# Collection.net
KiCad netlist of a schematic drawn in Altium Designer
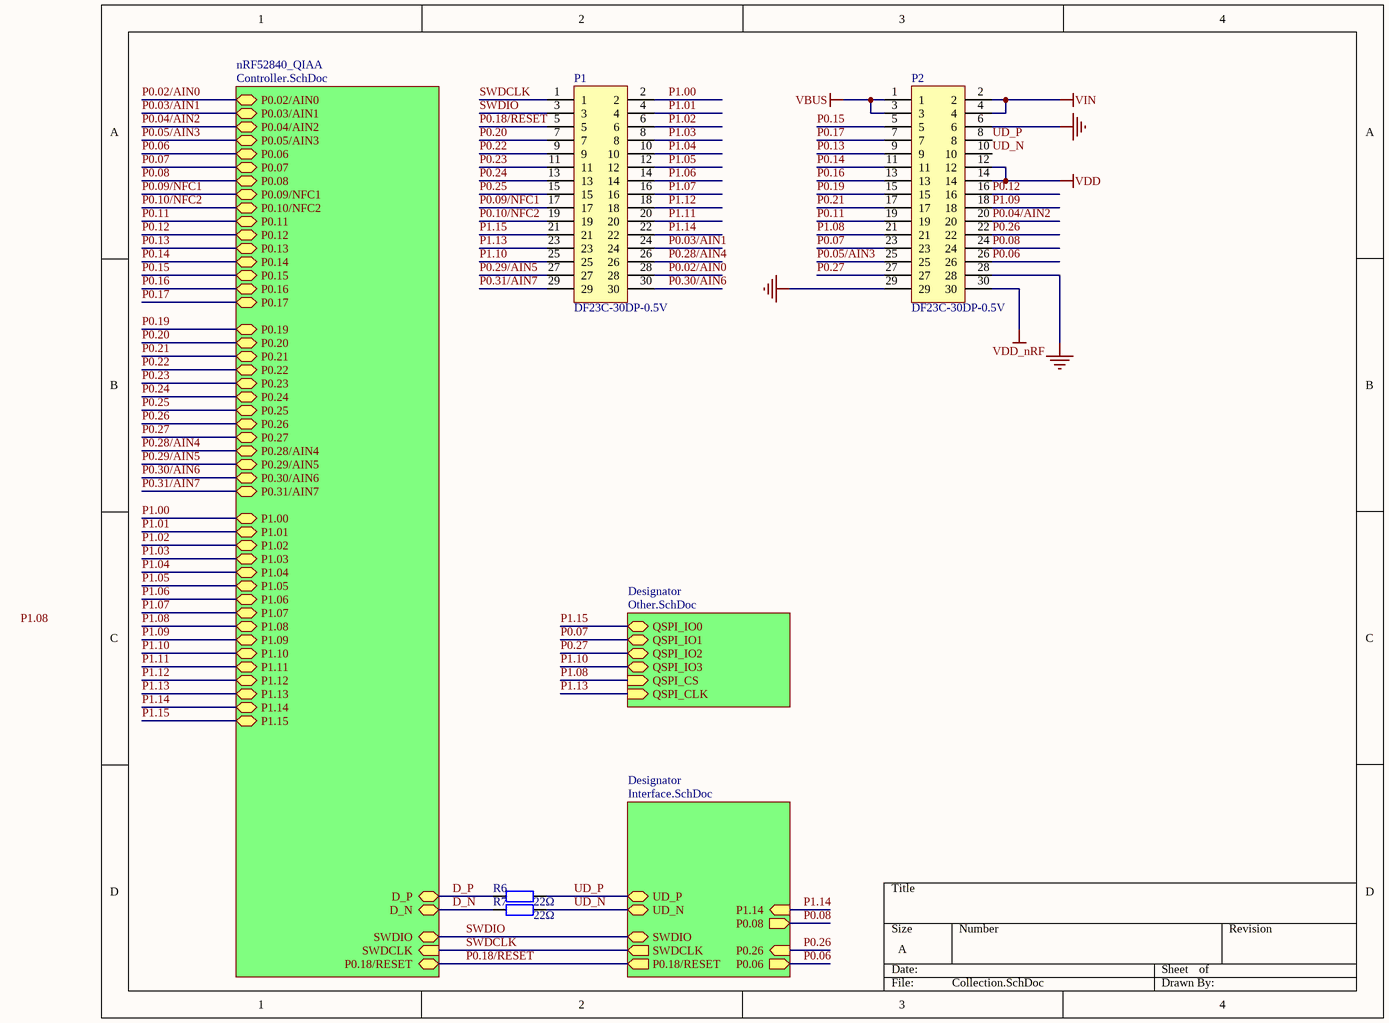
[diagram p0: Collection.SchDoc]

(export (version "E")
  (design (tool "Eeschema 10.0.6"))
  (components
    (comp (ref "P1")
      (value "DF23C-30DP-0.5V")
      (footprint "DF23C-30DP-0.5V")
      (libsource (lib "LocalLib") (part "DF23C-30DP-0.5V"))
    )
    (comp (ref "P2")
      (value "DF23C-30DP-0.5V")
      (footprint "DF23C-30DP-0.5V")
      (libsource (lib "LocalLib") (part "DF23C-30DP-0.5V"))
    )
    (comp (ref "R6")
      (value "22Ω")
      (footprint "0402_R")
      (description "Chip Resistor")
      (fields (field (name "Comment") "22Ω (22R0) ±1%"))
      (libsource (lib "LocalLib") (part "0402 22Ω (22R0) 1%"))
    )
    (comp (ref "R7")
      (value "22Ω")
      (footprint "0402_R")
      (description "Chip Resistor")
      (fields (field (name "Comment") "22Ω (22R0) ±1%"))
      (libsource (lib "LocalLib") (part "0402 22Ω (22R0) 1%"))
    )
  )
  (nets
    (net (code "1") (name "/D_N") (class "Default")
      (node (ref "R7") (pin "1") (pinfunction "1_1") (pintype "passive"))
    )
    (net (code "2") (name "/D_P") (class "Default")
      (node (ref "R6") (pin "1") (pinfunction "1_1") (pintype "passive"))
    )
    (net (code "3") (name "/P0.02{slash}AIN0") (class "Default")
      (node (ref "P1") (pin "28") (pinfunction "28_28") (pintype "passive"))
    )
    (net (code "4") (name "/P0.03{slash}AIN1") (class "Default")
      (node (ref "P1") (pin "24") (pinfunction "24_24") (pintype "passive"))
    )
    (net (code "5") (name "/P0.04{slash}AIN2") (class "Default")
      (node (ref "P2") (pin "20") (pinfunction "20_20") (pintype "passive"))
    )
    (net (code "6") (name "/P0.05{slash}AIN3") (class "Default")
      (node (ref "P2") (pin "25") (pinfunction "25_25") (pintype "passive"))
    )
    (net (code "7") (name "/P0.06") (class "Default")
      (node (ref "P2") (pin "26") (pinfunction "26_26") (pintype "passive"))
    )
    (net (code "8") (name "/P0.07") (class "Default")
      (node (ref "P2") (pin "23") (pinfunction "23_23") (pintype "passive"))
    )
    (net (code "9") (name "/P0.08") (class "Default")
      (node (ref "P2") (pin "24") (pinfunction "24_24") (pintype "passive"))
    )
    (net (code "10") (name "/P0.09{slash}NFC1") (class "Default")
      (node (ref "P1") (pin "17") (pinfunction "17_17") (pintype "passive"))
    )
    (net (code "11") (name "/P0.10{slash}NFC2") (class "Default")
      (node (ref "P1") (pin "19") (pinfunction "19_19") (pintype "passive"))
    )
    (net (code "12") (name "/P0.11") (class "Default")
      (node (ref "P2") (pin "19") (pinfunction "19_19") (pintype "passive"))
    )
    (net (code "13") (name "/P0.12") (class "Default")
      (node (ref "P2") (pin "16") (pinfunction "16_16") (pintype "passive"))
    )
    (net (code "14") (name "/P0.13") (class "Default")
      (node (ref "P2") (pin "9") (pinfunction "9_9") (pintype "passive"))
    )
    (net (code "15") (name "/P0.14") (class "Default")
      (node (ref "P2") (pin "11") (pinfunction "11_11") (pintype "passive"))
    )
    (net (code "16") (name "/P0.15") (class "Default")
      (node (ref "P2") (pin "5") (pinfunction "5_5") (pintype "passive"))
    )
    (net (code "17") (name "/P0.16") (class "Default")
      (node (ref "P2") (pin "13") (pinfunction "13_13") (pintype "passive"))
    )
    (net (code "18") (name "/P0.17") (class "Default")
      (node (ref "P2") (pin "7") (pinfunction "7_7") (pintype "passive"))
    )
    (net (code "19") (name "/P0.18{slash}RESET") (class "Default")
      (node (ref "P1") (pin "5") (pinfunction "5_5") (pintype "passive"))
    )
    (net (code "20") (name "/P0.19") (class "Default")
      (node (ref "P2") (pin "15") (pinfunction "15_15") (pintype "passive"))
    )
    (net (code "21") (name "/P0.20") (class "Default")
      (node (ref "P1") (pin "7") (pinfunction "7_7") (pintype "passive"))
    )
    (net (code "22") (name "/P0.21") (class "Default")
      (node (ref "P2") (pin "17") (pinfunction "17_17") (pintype "passive"))
    )
    (net (code "23") (name "/P0.22") (class "Default")
      (node (ref "P1") (pin "9") (pinfunction "9_9") (pintype "passive"))
    )
    (net (code "24") (name "/P0.23") (class "Default")
      (node (ref "P1") (pin "11") (pinfunction "11_11") (pintype "passive"))
    )
    (net (code "25") (name "/P0.24") (class "Default")
      (node (ref "P1") (pin "13") (pinfunction "13_13") (pintype "passive"))
    )
    (net (code "26") (name "/P0.25") (class "Default")
      (node (ref "P1") (pin "15") (pinfunction "15_15") (pintype "passive"))
    )
    (net (code "27") (name "/P0.26") (class "Default")
      (node (ref "P2") (pin "22") (pinfunction "22_22") (pintype "passive"))
    )
    (net (code "28") (name "/P0.27") (class "Default")
      (node (ref "P2") (pin "27") (pinfunction "27_27") (pintype "passive"))
    )
    (net (code "29") (name "/P0.28{slash}AIN4") (class "Default")
      (node (ref "P1") (pin "26") (pinfunction "26_26") (pintype "passive"))
    )
    (net (code "30") (name "/P0.29{slash}AIN5") (class "Default")
      (node (ref "P1") (pin "27") (pinfunction "27_27") (pintype "passive"))
    )
    (net (code "31") (name "/P0.30{slash}AIN6") (class "Default")
      (node (ref "P1") (pin "30") (pinfunction "30_30") (pintype "passive"))
    )
    (net (code "32") (name "/P0.31{slash}AIN7") (class "Default")
      (node (ref "P1") (pin "29") (pinfunction "29_29") (pintype "passive"))
    )
    (net (code "33") (name "/P1.00") (class "Default")
      (node (ref "P1") (pin "2") (pinfunction "2_2") (pintype "passive"))
    )
    (net (code "34") (name "/P1.01") (class "Default")
      (node (ref "P1") (pin "4") (pinfunction "4_4") (pintype "passive"))
    )
    (net (code "35") (name "/P1.02") (class "Default")
      (node (ref "P1") (pin "6") (pinfunction "6_6") (pintype "passive"))
    )
    (net (code "36") (name "/P1.03") (class "Default")
      (node (ref "P1") (pin "8") (pinfunction "8_8") (pintype "passive"))
    )
    (net (code "37") (name "/P1.04") (class "Default")
      (node (ref "P1") (pin "10") (pinfunction "10_10") (pintype "passive"))
    )
    (net (code "38") (name "/P1.05") (class "Default")
      (node (ref "P1") (pin "12") (pinfunction "12_12") (pintype "passive"))
    )
    (net (code "39") (name "/P1.06") (class "Default")
      (node (ref "P1") (pin "14") (pinfunction "14_14") (pintype "passive"))
    )
    (net (code "40") (name "/P1.07") (class "Default")
      (node (ref "P1") (pin "16") (pinfunction "16_16") (pintype "passive"))
    )
    (net (code "41") (name "/P1.08") (class "Default")
      (node (ref "P2") (pin "21") (pinfunction "21_21") (pintype "passive"))
    )
    (net (code "42") (name "/P1.09") (class "Default")
      (node (ref "P2") (pin "18") (pinfunction "18_18") (pintype "passive"))
    )
    (net (code "43") (name "/P1.10") (class "Default")
      (node (ref "P1") (pin "25") (pinfunction "25_25") (pintype "passive"))
    )
    (net (code "44") (name "/P1.11") (class "Default")
      (node (ref "P1") (pin "20") (pinfunction "20_20") (pintype "passive"))
    )
    (net (code "45") (name "/P1.12") (class "Default")
      (node (ref "P1") (pin "18") (pinfunction "18_18") (pintype "passive"))
    )
    (net (code "46") (name "/P1.13") (class "Default")
      (node (ref "P1") (pin "23") (pinfunction "23_23") (pintype "passive"))
    )
    (net (code "47") (name "/P1.14") (class "Default")
      (node (ref "P1") (pin "22") (pinfunction "22_22") (pintype "passive"))
    )
    (net (code "48") (name "/P1.15") (class "Default")
      (node (ref "P1") (pin "21") (pinfunction "21_21") (pintype "passive"))
    )
    (net (code "49") (name "/SWDCLK") (class "Default")
      (node (ref "P1") (pin "1") (pinfunction "1_1") (pintype "passive"))
    )
    (net (code "50") (name "/SWDIO") (class "Default")
      (node (ref "P1") (pin "3") (pinfunction "3_3") (pintype "passive"))
    )
    (net (code "51") (name "/UD_N") (class "Default")
      (node (ref "P2") (pin "10") (pinfunction "10_10") (pintype "passive"))
      (node (ref "R7") (pin "2") (pinfunction "2_2") (pintype "passive"))
    )
    (net (code "52") (name "/UD_P") (class "Default")
      (node (ref "P2") (pin "8") (pinfunction "8_8") (pintype "passive"))
      (node (ref "R6") (pin "2") (pinfunction "2_2") (pintype "passive"))
    )
    (net (code "53") (name "GND") (class "Default")
      (node (ref "P2") (pin "28") (pinfunction "28_28") (pintype "passive"))
      (node (ref "P2") (pin "29") (pinfunction "29_29") (pintype "passive"))
      (node (ref "P2") (pin "6") (pinfunction "6_6") (pintype "passive"))
    )
    (net (code "54") (name "VBUS") (class "Default")
      (node (ref "P2") (pin "1") (pinfunction "1_1") (pintype "passive"))
      (node (ref "P2") (pin "3") (pinfunction "3_3") (pintype "passive"))
    )
    (net (code "55") (name "VDD") (class "Default")
      (node (ref "P2") (pin "12") (pinfunction "12_12") (pintype "passive"))
      (node (ref "P2") (pin "14") (pinfunction "14_14") (pintype "passive"))
    )
    (net (code "56") (name "VDD_nRF") (class "Default")
      (node (ref "P2") (pin "30") (pinfunction "30_30") (pintype "passive"))
    )
    (net (code "57") (name "VIN") (class "Default")
      (node (ref "P2") (pin "2") (pinfunction "2_2") (pintype "passive"))
      (node (ref "P2") (pin "4") (pinfunction "4_4") (pintype "passive"))
    )
  )
)
